# Power.net
KiCad netlist of a schematic drawn in Altium Designer
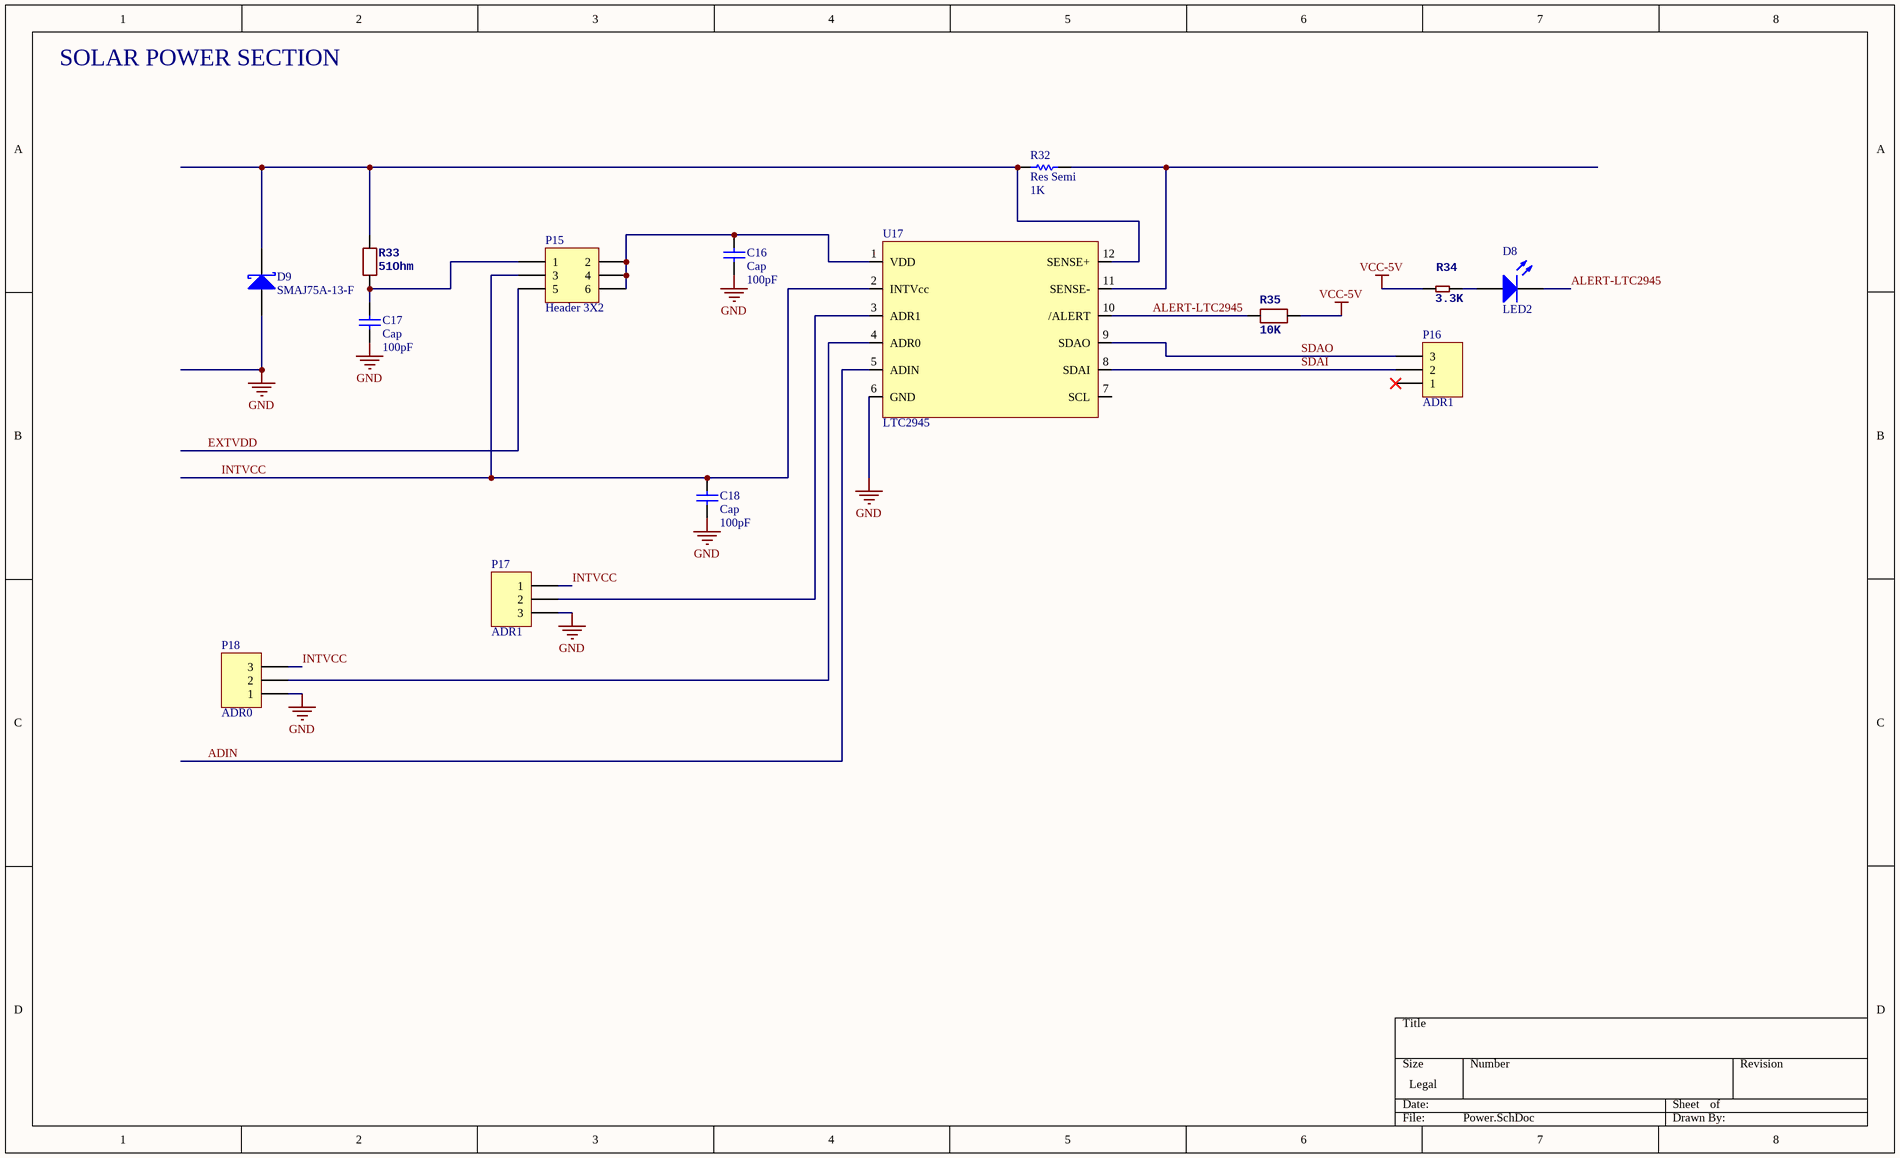
[diagram p0: Power.SchDoc]

(export (version "E")
  (design (tool "Eeschema 10.0.6"))
  (components
    (comp (ref "C16")
      (value "Cap")
      (footprint "RAD-0.3")
      (description "Capacitor")
      (fields (field (name "ALTIUM_VALUE") "100pF") (field (name "PUBLISHER") "Altium Limited"))
      (libsource (lib "Miscellaneous Devices") (part "Cap"))
    )
    (comp (ref "C17")
      (value "Cap")
      (footprint "RAD-0.3")
      (description "Capacitor")
      (fields (field (name "ALTIUM_VALUE") "100pF") (field (name "PUBLISHER") "Altium Limited"))
      (libsource (lib "Miscellaneous Devices") (part "Cap"))
    )
    (comp (ref "C18")
      (value "Cap")
      (footprint "RAD-0.3")
      (description "Capacitor")
      (fields (field (name "ALTIUM_VALUE") "100pF") (field (name "PUBLISHER") "Altium Limited"))
      (libsource (lib "Miscellaneous Devices") (part "Cap"))
    )
    (comp (ref "D8")
      (value "LED2")
      (footprint "3.2X1.6X1.1")
      (description "Typical RED, GREEN, YELLOW, AMBER GaAs LED")
      (fields (field (name "PUBLISHER") "Altium Limited"))
      (libsource (lib "Miscellaneous Devices") (part "LED2"))
    )
    (comp (ref "D9")
      (value "SMAJ75A-13-F")
      (footprint "SMAJ5.0-TVS")
      (description "SMA")
      (fields (field (name "PUBLISHER") "Altium Limited"))
      (libsource (lib "Miscellaneous Devices") (part "D Schottky"))
    )
    (comp (ref "P15")
      (value "Header 3X2")
      (footprint "HDR2X3")
      (description "Header, 3-Pin, Dual row")
      (fields (field (name "PUBLISHER") "Altium Limited"))
      (libsource (lib "Miscellaneous Connectors") (part "Header 3X2"))
    )
    (comp (ref "P16")
      (value "ADR1")
      (footprint "HDR1X3")
      (description "Header, 3-Pin")
      (fields (field (name "PUBLISHER") "Altium Limited"))
      (libsource (lib "") (part "Header 3_1"))
    )
    (comp (ref "P17")
      (value "ADR1")
      (footprint "HDR1X3")
      (description "Header, 3-Pin")
      (fields (field (name "PUBLISHER") "Altium Limited"))
      (libsource (lib "Miscellaneous Connectors") (part "Header 3"))
    )
    (comp (ref "P18")
      (value "ADR0")
      (footprint "HDR1X3")
      (description "Header, 3-Pin")
      (fields (field (name "PUBLISHER") "Altium Limited"))
      (libsource (lib "") (part "Header 3_2"))
    )
    (comp (ref "R32")
      (value "Res Semi")
      (footprint "AXIAL-0.5")
      (description "Semiconductor Resistor")
      (fields (field (name "ALTIUM_VALUE") "1K") (field (name "PUBLISHER") "Altium Limited"))
      (libsource (lib "Miscellaneous Devices") (part "Res Semi"))
    )
    (comp (ref "R33")
      (value "51Ohm")
      (footprint "R0805")
      (libsource (lib "microbuilder") (part "RESISTOR0805_NOOUTLINE"))
    )
    (comp (ref "R34")
      (value "3.3K")
      (footprint "C1206")
      (fields (field (name "MPN") "RC0402FR-07330RL"))
      (libsource (lib "Seeed-Resistor") (part "SMD-RES-330R-1%-1/16W(0402)"))
    )
    (comp (ref "R35")
      (value "10K")
      (footprint "R0805")
      (libsource (lib "microbuilder") (part "RESISTOR0805_NOOUTLINE"))
    )
    (comp (ref "U17")
      (value "LTC2945")
      (description "V I P Monitor I2C Interface")
      (libsource (lib "Solar_Schlib1") (part "LTC2945"))
    )
  )
  (nets
    (net (code "1") (name "/ADIN") (class "Default")
      (node (ref "U17") (pin "5") (pinfunction "ADIN_5") (pintype "power_in"))
    )
    (net (code "2") (name "/ALERT-LTC2945") (class "Default")
      (node (ref "D8") (pin "2") (pinfunction "K_2") (pintype "passive"))
      (node (ref "R35") (pin "1") (pinfunction "1_1") (pintype "passive"))
      (node (ref "U17") (pin "10") (pinfunction "/ALERT_10") (pintype "power_in"))
    )
    (net (code "3") (name "/EXTVDD") (class "Default")
      (node (ref "P15") (pin "5") (pinfunction "5_5") (pintype "passive"))
    )
    (net (code "4") (name "/INTVCC") (class "Default")
      (node (ref "C18") (pin "2") (pinfunction "2_2") (pintype "passive"))
      (node (ref "P15") (pin "3") (pinfunction "3_3") (pintype "passive"))
      (node (ref "P17") (pin "1") (pinfunction "1_1") (pintype "passive"))
      (node (ref "P18") (pin "3") (pinfunction "3_3") (pintype "passive"))
      (node (ref "U17") (pin "2") (pinfunction "INTVcc_2") (pintype "power_in"))
    )
    (net (code "5") (name "/SDAI") (class "Default")
      (node (ref "P16") (pin "2") (pinfunction "2_2") (pintype "passive"))
      (node (ref "U17") (pin "8") (pinfunction "SDAI_8") (pintype "power_in"))
    )
    (net (code "6") (name "/SDAO") (class "Default")
      (node (ref "P16") (pin "3") (pinfunction "3_3") (pintype "passive"))
      (node (ref "U17") (pin "9") (pinfunction "SDAO_9") (pintype "power_in"))
    )
    (net (code "7") (name "GND") (class "Default")
      (node (ref "C16") (pin "1") (pinfunction "1_1") (pintype "passive"))
      (node (ref "C17") (pin "1") (pinfunction "1_1") (pintype "passive"))
      (node (ref "C18") (pin "1") (pinfunction "1_1") (pintype "passive"))
      (node (ref "D9") (pin "1") (pinfunction "A_1") (pintype "passive"))
      (node (ref "P17") (pin "3") (pinfunction "3_3") (pintype "passive"))
      (node (ref "P18") (pin "1") (pinfunction "1_1") (pintype "passive"))
      (node (ref "U17") (pin "6") (pinfunction "GND_6") (pintype "power_in"))
    )
    (net (code "8") (name "Net-(C17-Pad2)") (class "Default")
      (node (ref "C17") (pin "2") (pinfunction "2_2") (pintype "passive"))
      (node (ref "P15") (pin "1") (pinfunction "1_1") (pintype "passive"))
      (node (ref "R33") (pin "2") (pinfunction "2_2") (pintype "passive"))
    )
    (net (code "9") (name "Net-(D8-A)") (class "Default")
      (node (ref "D8") (pin "1") (pinfunction "A_1") (pintype "passive"))
      (node (ref "R34") (pin "2") (pinfunction "2_2") (pintype "passive"))
    )
    (net (code "10") (name "Net-(D9-K)") (class "Default")
      (node (ref "D9") (pin "2") (pinfunction "K_2") (pintype "passive"))
      (node (ref "R32") (pin "1") (pinfunction "1_1") (pintype "passive"))
      (node (ref "R33") (pin "1") (pinfunction "1_1") (pintype "passive"))
      (node (ref "U17") (pin "12") (pinfunction "SENSE+_12") (pintype "power_in"))
    )
    (net (code "11") (name "Net-(U17-ADR0)") (class "Default")
      (node (ref "P18") (pin "2") (pinfunction "2_2") (pintype "passive"))
      (node (ref "U17") (pin "4") (pinfunction "ADR0_4") (pintype "power_in"))
    )
    (net (code "12") (name "Net-(U17-ADR1)") (class "Default")
      (node (ref "P17") (pin "2") (pinfunction "2_2") (pintype "passive"))
      (node (ref "U17") (pin "3") (pinfunction "ADR1_3") (pintype "power_in"))
    )
    (net (code "13") (name "Net-(U17-SENSE-)") (class "Default")
      (node (ref "R32") (pin "2") (pinfunction "2_2") (pintype "passive"))
      (node (ref "U17") (pin "11") (pinfunction "SENSE-_11") (pintype "power_in"))
    )
    (net (code "14") (name "Net-(U17-VDD)") (class "Default")
      (node (ref "C16") (pin "2") (pinfunction "2_2") (pintype "passive"))
      (node (ref "P15") (pin "2") (pinfunction "2_2") (pintype "passive"))
      (node (ref "P15") (pin "4") (pinfunction "4_4") (pintype "passive"))
      (node (ref "P15") (pin "6") (pinfunction "6_6") (pintype "passive"))
      (node (ref "U17") (pin "1") (pinfunction "VDD_1") (pintype "power_in"))
    )
    (net (code "15") (name "VCC-5V") (class "Default")
      (node (ref "R34") (pin "1") (pinfunction "1_1") (pintype "passive"))
      (node (ref "R35") (pin "2") (pinfunction "2_2") (pintype "passive"))
    )
    (net (code "16") (name "unconnected-(P16-Pad1)") (class "Default")
      (node (ref "P16") (pin "1") (pinfunction "1_1") (pintype "passive+no_connect"))
    )
    (net (code "17") (name "unconnected-(U17-SCL-Pad7)") (class "Default")
      (node (ref "U17") (pin "7") (pinfunction "SCL_7") (pintype "power_in"))
    )
  )
)
